# RK.net
KiCad netlist of a schematic drawn in EAGLE
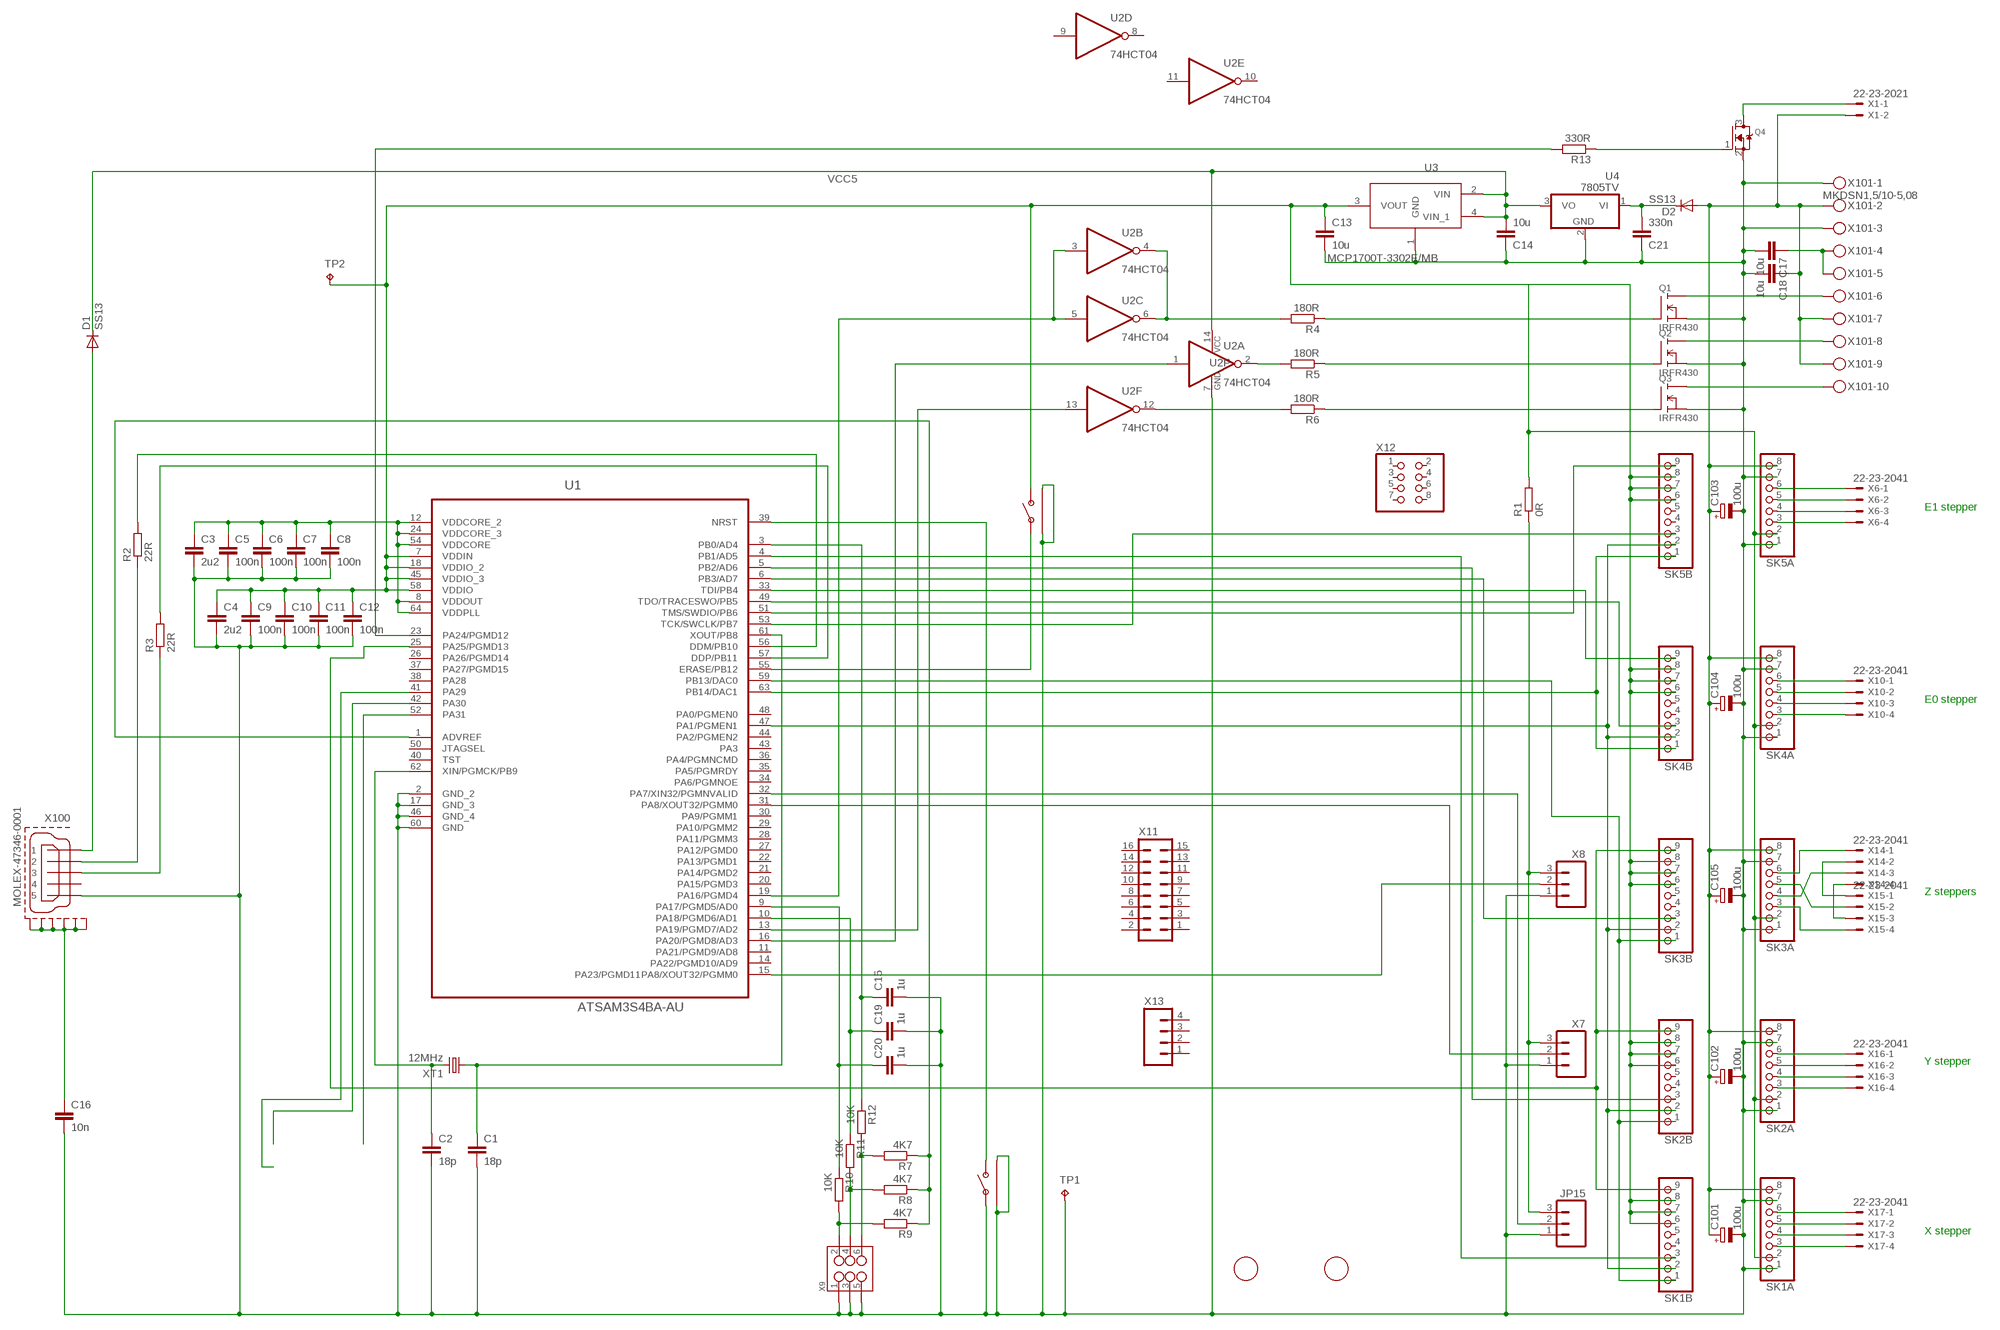
[diagram p0: schematic, sheet 1]

(export (version "E")
  (design (tool "Eeschema 10.0.6"))
  (components
    (comp (ref "C1")
      (value "18p")
      (footprint "eagle-import:C0603")
      (libsource (lib "eagle-import") (part "C-EUC0603"))
    )
    (comp (ref "C2")
      (value "18p")
      (footprint "eagle-import:C0603")
      (libsource (lib "eagle-import") (part "C-EUC0603"))
    )
    (comp (ref "C3")
      (value "2u2")
      (footprint "eagle-import:C0603")
      (libsource (lib "eagle-import") (part "C-EUC0603"))
    )
    (comp (ref "C4")
      (value "2u2")
      (footprint "eagle-import:C0603")
      (libsource (lib "eagle-import") (part "C-EUC0603"))
    )
    (comp (ref "C5")
      (value "100n")
      (footprint "eagle-import:C0603")
      (libsource (lib "eagle-import") (part "C-EUC0603"))
    )
    (comp (ref "C6")
      (value "100n")
      (footprint "eagle-import:C0603")
      (libsource (lib "eagle-import") (part "C-EUC0603"))
    )
    (comp (ref "C7")
      (value "100n")
      (footprint "eagle-import:C0603")
      (libsource (lib "eagle-import") (part "C-EUC0603"))
    )
    (comp (ref "C8")
      (value "100n")
      (footprint "eagle-import:C0603")
      (libsource (lib "eagle-import") (part "C-EUC0603"))
    )
    (comp (ref "C9")
      (value "100n")
      (footprint "eagle-import:C0603")
      (libsource (lib "eagle-import") (part "C-EUC0603"))
    )
    (comp (ref "C10")
      (value "100n")
      (footprint "eagle-import:C0603")
      (libsource (lib "eagle-import") (part "C-EUC0603"))
    )
    (comp (ref "C11")
      (value "100n")
      (footprint "eagle-import:C0603")
      (libsource (lib "eagle-import") (part "C-EUC0603"))
    )
    (comp (ref "C12")
      (value "100n")
      (footprint "eagle-import:C0603")
      (libsource (lib "eagle-import") (part "C-EUC0603"))
    )
    (comp (ref "C13")
      (value "10u")
      (footprint "eagle-import:C0805")
      (libsource (lib "eagle-import") (part "C-EUC0805"))
    )
    (comp (ref "C14")
      (value "10u")
      (footprint "eagle-import:C0805")
      (libsource (lib "eagle-import") (part "C-EUC0805"))
    )
    (comp (ref "C15")
      (value "1u")
      (footprint "eagle-import:C0603")
      (libsource (lib "eagle-import") (part "C-EUC0603"))
    )
    (comp (ref "C16")
      (value "10n")
      (footprint "eagle-import:C0603")
      (libsource (lib "eagle-import") (part "C-EUC0603"))
    )
    (comp (ref "C17")
      (value "10u")
      (footprint "eagle-import:C0805K")
      (libsource (lib "eagle-import") (part "C-EUC0805K"))
    )
    (comp (ref "C18")
      (value "10u")
      (footprint "eagle-import:C0805K")
      (libsource (lib "eagle-import") (part "C-EUC0805K"))
    )
    (comp (ref "C19")
      (value "1u")
      (footprint "eagle-import:C0603")
      (libsource (lib "eagle-import") (part "C-EUC0603"))
    )
    (comp (ref "C20")
      (value "1u")
      (footprint "eagle-import:C0603")
      (libsource (lib "eagle-import") (part "C-EUC0603"))
    )
    (comp (ref "C21")
      (value "330n")
      (footprint "eagle-import:C0805")
      (libsource (lib "eagle-import") (part "C-EUC0805"))
    )
    (comp (ref "C101")
      (value "100u")
      (footprint "eagle-import:PANASONIC_D")
      (libsource (lib "eagle-import") (part "CPOL-EUD"))
    )
    (comp (ref "C102")
      (value "100u")
      (footprint "eagle-import:PANASONIC_D")
      (libsource (lib "eagle-import") (part "CPOL-EUD"))
    )
    (comp (ref "C103")
      (value "100u")
      (footprint "eagle-import:PANASONIC_D")
      (libsource (lib "eagle-import") (part "CPOL-EUD"))
    )
    (comp (ref "C104")
      (value "100u")
      (footprint "eagle-import:PANASONIC_D")
      (libsource (lib "eagle-import") (part "CPOL-EUD"))
    )
    (comp (ref "C105")
      (value "100u")
      (footprint "eagle-import:PANASONIC_D")
      (libsource (lib "eagle-import") (part "CPOL-EUD"))
    )
    (comp (ref "D1")
      (value "SS13")
      (footprint "eagle-import:DO214AC")
      (libsource (lib "eagle-import") (part "DIODE-DO214AC"))
    )
    (comp (ref "D2")
      (value "SS13")
      (footprint "eagle-import:DO214AC")
      (libsource (lib "eagle-import") (part "DIODE-DO214AC"))
    )
    (comp (ref "JP15")
      (value "M03PTH")
      (footprint "eagle-import:1X03")
      (libsource (lib "eagle-import") (part "M03PTH"))
    )
    (comp (ref "Q1")
      (value "IRFR430")
      (footprint "eagle-import:DPAK")
      (libsource (lib "eagle-import") (part "IRFR430"))
    )
    (comp (ref "Q2")
      (value "IRFR430")
      (footprint "eagle-import:DPAK")
      (libsource (lib "eagle-import") (part "IRFR430"))
    )
    (comp (ref "Q3")
      (value "IRFR430")
      (footprint "eagle-import:DPAK")
      (libsource (lib "eagle-import") (part "IRFR430"))
    )
    (comp (ref "Q4")
      (value "MOSFET-NREFLOW")
      (footprint "eagle-import:SOT23")
      (libsource (lib "eagle-import") (part "MOSFET-NREFLOW"))
    )
    (comp (ref "R1")
      (value "0R")
      (footprint "eagle-import:R0603")
      (libsource (lib "eagle-import") (part "R-EU_R0603"))
    )
    (comp (ref "R2")
      (value "22R")
      (footprint "eagle-import:R0603")
      (libsource (lib "eagle-import") (part "R-EU_R0603"))
    )
    (comp (ref "R3")
      (value "22R")
      (footprint "eagle-import:R0603")
      (libsource (lib "eagle-import") (part "R-EU_R0603"))
    )
    (comp (ref "R4")
      (value "180R")
      (footprint "eagle-import:R0603")
      (libsource (lib "eagle-import") (part "R-EU_R0603"))
    )
    (comp (ref "R5")
      (value "180R")
      (footprint "eagle-import:R0603")
      (libsource (lib "eagle-import") (part "R-EU_R0603"))
    )
    (comp (ref "R6")
      (value "180R")
      (footprint "eagle-import:R0603")
      (libsource (lib "eagle-import") (part "R-EU_R0603"))
    )
    (comp (ref "R7")
      (value "4K7")
      (footprint "eagle-import:R0603")
      (libsource (lib "eagle-import") (part "R-EU_R0603"))
    )
    (comp (ref "R8")
      (value "4K7")
      (footprint "eagle-import:R0603")
      (libsource (lib "eagle-import") (part "R-EU_R0603"))
    )
    (comp (ref "R9")
      (value "4K7")
      (footprint "eagle-import:R0603")
      (libsource (lib "eagle-import") (part "R-EU_R0603"))
    )
    (comp (ref "R10")
      (value "10K")
      (footprint "eagle-import:R0603")
      (libsource (lib "eagle-import") (part "R-EU_R0603"))
    )
    (comp (ref "R11")
      (value "10K")
      (footprint "eagle-import:R0603")
      (libsource (lib "eagle-import") (part "R-EU_R0603"))
    )
    (comp (ref "R12")
      (value "10K")
      (footprint "eagle-import:R0603")
      (libsource (lib "eagle-import") (part "R-EU_R0603"))
    )
    (comp (ref "R13")
      (value "330R")
      (footprint "eagle-import:R0603")
      (libsource (lib "eagle-import") (part "R-EU_R0603"))
    )
    (comp (ref "SK1A")
      (value "PINHD-1X8BIG")
      (footprint "eagle-import:1X08-BIG")
      (libsource (lib "eagle-import") (part "PINHD-1X8BIG"))
    )
    (comp (ref "SK1B")
      (value "PINHD-1X9")
      (footprint "eagle-import:1X09-BIG")
      (libsource (lib "eagle-import") (part "PINHD-1X9"))
    )
    (comp (ref "SK2A")
      (value "PINHD-1X8BIG")
      (footprint "eagle-import:1X08-BIG")
      (libsource (lib "eagle-import") (part "PINHD-1X8BIG"))
    )
    (comp (ref "SK2B")
      (value "PINHD-1X9")
      (footprint "eagle-import:1X09-BIG")
      (libsource (lib "eagle-import") (part "PINHD-1X9"))
    )
    (comp (ref "SK3A")
      (value "PINHD-1X8BIG")
      (footprint "eagle-import:1X08-BIG")
      (libsource (lib "eagle-import") (part "PINHD-1X8BIG"))
    )
    (comp (ref "SK3B")
      (value "PINHD-1X9")
      (footprint "eagle-import:1X09-BIG")
      (libsource (lib "eagle-import") (part "PINHD-1X9"))
    )
    (comp (ref "SK4A")
      (value "PINHD-1X8BIG")
      (footprint "eagle-import:1X08-BIG")
      (libsource (lib "eagle-import") (part "PINHD-1X8BIG"))
    )
    (comp (ref "SK4B")
      (value "PINHD-1X9")
      (footprint "eagle-import:1X09-BIG")
      (libsource (lib "eagle-import") (part "PINHD-1X9"))
    )
    (comp (ref "SK5A")
      (value "PINHD-1X8BIG")
      (footprint "eagle-import:1X08-BIG")
      (libsource (lib "eagle-import") (part "PINHD-1X8BIG"))
    )
    (comp (ref "SK5B")
      (value "PINHD-1X9")
      (footprint "eagle-import:1X09-BIG")
      (libsource (lib "eagle-import") (part "PINHD-1X9"))
    )
    (comp (ref "TP1")
      (value "TPPAD1-10")
      (footprint "eagle-import:P1-10")
      (libsource (lib "eagle-import") (part "TPPAD1-10"))
    )
    (comp (ref "TP2")
      (value "TPPAD1-10")
      (footprint "eagle-import:P1-10")
      (libsource (lib "eagle-import") (part "TPPAD1-10"))
    )
    (comp (ref "U$1")
      (value "FIDUCIAL")
      (footprint "eagle-import:FIDUCIAL_1MM")
      (libsource (lib "eagle-import") (part "FIDUCIAL"))
    )
    (comp (ref "U$2")
      (value "FIDUCIAL")
      (footprint "eagle-import:FIDUCIAL_1MM")
      (libsource (lib "eagle-import") (part "FIDUCIAL"))
    )
    (comp (ref "U$3")
      (value "ALPS-SKHHLUA010")
      (footprint "eagle-import:SKHHLUA010")
      (libsource (lib "eagle-import") (part "ALPS-SKHHLUA010"))
    )
    (comp (ref "U$4")
      (value "ALPS-SKHHLUA010")
      (footprint "eagle-import:SKHHLUA010")
      (libsource (lib "eagle-import") (part "ALPS-SKHHLUA010"))
    )
    (comp (ref "U1")
      (value "ATSAM3S4BA-AU")
      (footprint "eagle-import:QFP50P1200X1200X160-64N")
      (libsource (lib "eagle-import") (part "ATSAM3S4BA-AU"))
    )
    (comp (ref "U2")
      (value "74HCT04")
      (footprint "eagle-import:TSSOP14")
      (libsource (lib "eagle-import") (part "7404"))
    )
    (comp (ref "U3")
      (value "MCP1700T-3302E/MB")
      (footprint "eagle-import:SOT150P400X160-4N")
      (fields (field (name "MPN") "MCP1702T-3302E/MB"))
      (libsource (lib "eagle-import") (part "MCP17-MCP1702T-3302E/MB"))
    )
    (comp (ref "U4")
      (value "7805TV")
      (footprint "eagle-import:TO220V")
      (libsource (lib "eagle-import") (part "78TV05"))
    )
    (comp (ref "X1")
      (value "22-23-2021")
      (footprint "eagle-import:22-23-2021")
      (fields (field (name "MF") "MOLEX"))
      (libsource (lib "eagle-import") (part "22-23-2021"))
    )
    (comp (ref "X6")
      (value "22-23-2041")
      (footprint "eagle-import:22-23-2041")
      (fields (field (name "MF") "MOLEX"))
      (libsource (lib "eagle-import") (part "22-23-2041"))
    )
    (comp (ref "X7")
      (value "M03PTH")
      (footprint "eagle-import:1X03")
      (libsource (lib "eagle-import") (part "M03PTH"))
    )
    (comp (ref "X8")
      (value "M03PTH")
      (footprint "eagle-import:1X03")
      (libsource (lib "eagle-import") (part "M03PTH"))
    )
    (comp (ref "X9")
      (value "M03X22X3_SILK_SM")
      (footprint "eagle-import:2X3")
      (libsource (lib "eagle-import") (part "M03X22X3_SILK_SM"))
    )
    (comp (ref "X10")
      (value "22-23-2041")
      (footprint "eagle-import:22-23-2041")
      (fields (field (name "MF") "MOLEX"))
      (libsource (lib "eagle-import") (part "22-23-2041"))
    )
    (comp (ref "X11")
      (value "MA08-2")
      (footprint "eagle-import:MA08-2")
      (libsource (lib "eagle-import") (part "MA08-2"))
    )
    (comp (ref "X12")
      (value "PINHD-2X4")
      (footprint "eagle-import:2X04")
      (libsource (lib "eagle-import") (part "PINHD-2X4"))
    )
    (comp (ref "X13")
      (value "M04PTH")
      (footprint "eagle-import:1X04")
      (libsource (lib "eagle-import") (part "M04PTH"))
    )
    (comp (ref "X14")
      (value "22-23-2041")
      (footprint "eagle-import:22-23-2041")
      (fields (field (name "MF") "MOLEX"))
      (libsource (lib "eagle-import") (part "22-23-2041"))
    )
    (comp (ref "X15")
      (value "22-23-2041")
      (footprint "eagle-import:22-23-2041")
      (fields (field (name "MF") "MOLEX"))
      (libsource (lib "eagle-import") (part "22-23-2041"))
    )
    (comp (ref "X16")
      (value "22-23-2041")
      (footprint "eagle-import:22-23-2041")
      (fields (field (name "MF") "MOLEX"))
      (libsource (lib "eagle-import") (part "22-23-2041"))
    )
    (comp (ref "X17")
      (value "22-23-2041")
      (footprint "eagle-import:22-23-2041")
      (fields (field (name "MF") "MOLEX"))
      (libsource (lib "eagle-import") (part "22-23-2041"))
    )
    (comp (ref "X100")
      (value "MOLEX-47346-0001")
      (footprint "eagle-import:MOLEX-47364-0001")
      (libsource (lib "eagle-import") (part "MOLEX-47346-0001"))
    )
    (comp (ref "X101")
      (value "MKDSN1,5/10-5,08")
      (footprint "eagle-import:MKDSN1,5_10-5,08")
      (fields (field (name "MPN") "SMKDSN1,5/10-5,08"))
      (libsource (lib "eagle-import") (part "MKDSN1,5/10-5,08"))
    )
    (comp (ref "XT1")
      (value "12MHz")
      (footprint "eagle-import:HC49U-V")
      (libsource (lib "eagle-import") (part "CRYSTALHC49U-V"))
    )
  )
  (nets
    (net (code "1") (name "/VCC5") (class "Default")
      (node (ref "C14") (pin "2") (pinfunction "2_2") (pintype "passive"))
      (node (ref "D1") (pin "C") (pinfunction "C_C") (pintype "passive"))
      (node (ref "U2") (pin "14") (pinfunction "VCC_14") (pintype "power_in"))
      (node (ref "U3") (pin "2") (pinfunction "VIN_2") (pintype "input"))
      (node (ref "U3") (pin "4") (pinfunction "VIN_1_4") (pintype "input"))
      (node (ref "U4") (pin "3") (pinfunction "VO_3") (pintype "passive"))
    )
    (net (code "2") (name "Net-(C16-Pad1)") (class "Default")
      (node (ref "C16") (pin "1") (pinfunction "1_1") (pintype "passive"))
      (node (ref "X100") (pin "GND1") (pinfunction "GND1_GND1") (pintype "bidirectional"))
      (node (ref "X100") (pin "GND2") (pinfunction "GND2_GND2") (pintype "bidirectional"))
      (node (ref "X100") (pin "GND3") (pinfunction "GND3_GND3") (pintype "bidirectional"))
      (node (ref "X100") (pin "GND4") (pinfunction "GND4_GND4") (pintype "bidirectional"))
      (node (ref "X100") (pin "GND5") (pinfunction "GND5_GND5") (pintype "bidirectional"))
      (node (ref "X100") (pin "GND6") (pinfunction "GND6_GND6") (pintype "bidirectional"))
    )
    (net (code "3") (name "Net-(D1-PadA)") (class "Default")
      (node (ref "D1") (pin "A") (pinfunction "A_A") (pintype "passive"))
      (node (ref "X100") (pin "1") (pinfunction "1_1") (pintype "input"))
    )
    (net (code "4") (name "Net-(JP15-Pad3)") (class "Default")
      (node (ref "JP15") (pin "3") (pinfunction "3_3") (pintype "passive"))
      (node (ref "R1") (pin "1") (pinfunction "1_1") (pintype "passive"))
      (node (ref "X7") (pin "3") (pinfunction "3_3") (pintype "passive"))
      (node (ref "X8") (pin "3") (pinfunction "3_3") (pintype "passive"))
    )
    (net (code "5") (name "Net-(Q1-D)") (class "Default")
      (node (ref "Q1") (pin "2") (pinfunction "D_2") (pintype "passive"))
      (node (ref "X101") (pin "6") (pinfunction "KL_6") (pintype "passive"))
    )
    (net (code "6") (name "Net-(Q1-G)") (class "Default")
      (node (ref "Q1") (pin "1") (pinfunction "G_1") (pintype "passive"))
      (node (ref "R4") (pin "1") (pinfunction "1_1") (pintype "passive"))
    )
    (net (code "7") (name "Net-(Q1-S)") (class "Default")
      (node (ref "C1") (pin "2") (pinfunction "2_2") (pintype "passive"))
      (node (ref "C10") (pin "2") (pinfunction "2_2") (pintype "passive"))
      (node (ref "C101") (pin "-") (pinfunction "-_-") (pintype "passive"))
      (node (ref "C102") (pin "-") (pinfunction "-_-") (pintype "passive"))
      (node (ref "C103") (pin "-") (pinfunction "-_-") (pintype "passive"))
      (node (ref "C104") (pin "-") (pinfunction "-_-") (pintype "passive"))
      (node (ref "C105") (pin "-") (pinfunction "-_-") (pintype "passive"))
      (node (ref "C11") (pin "2") (pinfunction "2_2") (pintype "passive"))
      (node (ref "C12") (pin "2") (pinfunction "2_2") (pintype "passive"))
      (node (ref "C13") (pin "2") (pinfunction "2_2") (pintype "passive"))
      (node (ref "C14") (pin "1") (pinfunction "1_1") (pintype "passive"))
      (node (ref "C15") (pin "2") (pinfunction "2_2") (pintype "passive"))
      (node (ref "C16") (pin "2") (pinfunction "2_2") (pintype "passive"))
      (node (ref "C17") (pin "2") (pinfunction "2_2") (pintype "passive"))
      (node (ref "C18") (pin "2") (pinfunction "2_2") (pintype "passive"))
      (node (ref "C19") (pin "2") (pinfunction "2_2") (pintype "passive"))
      (node (ref "C2") (pin "2") (pinfunction "2_2") (pintype "passive"))
      (node (ref "C20") (pin "2") (pinfunction "2_2") (pintype "passive"))
      (node (ref "C21") (pin "1") (pinfunction "1_1") (pintype "passive"))
      (node (ref "C3") (pin "2") (pinfunction "2_2") (pintype "passive"))
      (node (ref "C4") (pin "2") (pinfunction "2_2") (pintype "passive"))
      (node (ref "C5") (pin "2") (pinfunction "2_2") (pintype "passive"))
      (node (ref "C6") (pin "2") (pinfunction "2_2") (pintype "passive"))
      (node (ref "C7") (pin "2") (pinfunction "2_2") (pintype "passive"))
      (node (ref "C8") (pin "2") (pinfunction "2_2") (pintype "passive"))
      (node (ref "C9") (pin "2") (pinfunction "2_2") (pintype "passive"))
      (node (ref "JP15") (pin "1") (pinfunction "1_1") (pintype "passive"))
      (node (ref "Q1") (pin "3") (pinfunction "S_3") (pintype "passive"))
      (node (ref "Q2") (pin "3") (pinfunction "S_3") (pintype "passive"))
      (node (ref "Q3") (pin "3") (pinfunction "S_3") (pintype "passive"))
      (node (ref "Q4") (pin "2") (pinfunction "S_2") (pintype "bidirectional"))
      (node (ref "SK1A") (pin "1") (pinfunction "1_1") (pintype "passive"))
      (node (ref "SK1A") (pin "7") (pinfunction "7_7") (pintype "passive"))
      (node (ref "SK2A") (pin "1") (pinfunction "1_1") (pintype "passive"))
      (node (ref "SK2A") (pin "7") (pinfunction "7_7") (pintype "passive"))
      (node (ref "SK3A") (pin "1") (pinfunction "1_1") (pintype "passive"))
      (node (ref "SK3A") (pin "7") (pinfunction "7_7") (pintype "passive"))
      (node (ref "SK4A") (pin "1") (pinfunction "1_1") (pintype "passive"))
      (node (ref "SK4A") (pin "7") (pinfunction "7_7") (pintype "passive"))
      (node (ref "SK5A") (pin "1") (pinfunction "1_1") (pintype "passive"))
      (node (ref "SK5A") (pin "7") (pinfunction "7_7") (pintype "passive"))
      (node (ref "TP1") (pin "TP") (pinfunction "TP_TP") (pintype "input"))
      (node (ref "U$3") (pin "P$1") (pinfunction "P$1_P$1") (pintype "bidirectional"))
      (node (ref "U$3") (pin "P$3") (pinfunction "P$3_P$3") (pintype "bidirectional"))
      (node (ref "U$3") (pin "P$4") (pinfunction "P$4_P$4") (pintype "bidirectional"))
      (node (ref "U$4") (pin "P$3") (pinfunction "P$3_P$3") (pintype "bidirectional"))
      (node (ref "U$4") (pin "P$4") (pinfunction "P$4_P$4") (pintype "bidirectional"))
      (node (ref "U1") (pin "17") (pinfunction "GND_3_17") (pintype "passive"))
      (node (ref "U1") (pin "2") (pinfunction "GND_2_2") (pintype "passive"))
      (node (ref "U1") (pin "46") (pinfunction "GND_4_46") (pintype "passive"))
      (node (ref "U1") (pin "60") (pinfunction "GND_60") (pintype "passive"))
      (node (ref "U2") (pin "7") (pinfunction "GND_7") (pintype "power_in"))
      (node (ref "U3") (pin "1") (pinfunction "GND_1") (pintype "power_in"))
      (node (ref "U4") (pin "2") (pinfunction "GND_2") (pintype "passive"))
      (node (ref "X100") (pin "5") (pinfunction "5_5") (pintype "input"))
      (node (ref "X101") (pin "1") (pinfunction "KL_1") (pintype "passive"))
      (node (ref "X101") (pin "3") (pinfunction "KL_3") (pintype "passive"))
      (node (ref "X7") (pin "1") (pinfunction "1_1") (pintype "passive"))
      (node (ref "X8") (pin "1") (pinfunction "1_1") (pintype "passive"))
      (node (ref "X9") (pin "1") (pinfunction "1_1") (pintype "bidirectional"))
      (node (ref "X9") (pin "3") (pinfunction "3_3") (pintype "bidirectional"))
      (node (ref "X9") (pin "5") (pinfunction "5_5") (pintype "bidirectional"))
    )
    (net (code "8") (name "Net-(Q2-D)") (class "Default")
      (node (ref "Q2") (pin "2") (pinfunction "D_2") (pintype "passive"))
      (node (ref "X101") (pin "8") (pinfunction "KL_8") (pintype "passive"))
    )
    (net (code "9") (name "Net-(Q2-G)") (class "Default")
      (node (ref "Q2") (pin "1") (pinfunction "G_1") (pintype "passive"))
      (node (ref "R5") (pin "1") (pinfunction "1_1") (pintype "passive"))
    )
    (net (code "10") (name "Net-(Q3-D)") (class "Default")
      (node (ref "Q3") (pin "2") (pinfunction "D_2") (pintype "passive"))
      (node (ref "X101") (pin "10") (pinfunction "KL_10") (pintype "passive"))
    )
    (net (code "11") (name "Net-(Q3-G)") (class "Default")
      (node (ref "Q3") (pin "1") (pinfunction "G_1") (pintype "passive"))
      (node (ref "R6") (pin "1") (pinfunction "1_1") (pintype "passive"))
    )
    (net (code "12") (name "Net-(Q4-D)") (class "Default")
      (node (ref "Q4") (pin "3") (pinfunction "D_3") (pintype "bidirectional"))
      (node (ref "X1") (pin "1") (pinfunction "S_1") (pintype "passive"))
    )
    (net (code "13") (name "Net-(Q4-G)") (class "Default")
      (node (ref "Q4") (pin "1") (pinfunction "G_1") (pintype "bidirectional"))
      (node (ref "R13") (pin "1") (pinfunction "1_1") (pintype "passive"))
    )
    (net (code "14") (name "Net-(R2-Pad1)") (class "Default")
      (node (ref "R2") (pin "1") (pinfunction "1_1") (pintype "passive"))
      (node (ref "X100") (pin "2") (pinfunction "2_2") (pintype "input"))
    )
    (net (code "15") (name "Net-(R3-Pad1)") (class "Default")
      (node (ref "R3") (pin "1") (pinfunction "1_1") (pintype "passive"))
      (node (ref "X100") (pin "3") (pinfunction "3_3") (pintype "input"))
    )
    (net (code "16") (name "Net-(R10-Pad2)") (class "Default")
      (node (ref "R10") (pin "2") (pinfunction "2_2") (pintype "passive"))
      (node (ref "R9") (pin "2") (pinfunction "2_2") (pintype "passive"))
      (node (ref "X9") (pin "2") (pinfunction "2_2") (pintype "bidirectional"))
    )
    (net (code "17") (name "Net-(R11-Pad2)") (class "Default")
      (node (ref "R11") (pin "2") (pinfunction "2_2") (pintype "passive"))
      (node (ref "R8") (pin "2") (pinfunction "2_2") (pintype "passive"))
      (node (ref "X9") (pin "4") (pinfunction "4_4") (pintype "bidirectional"))
    )
    (net (code "18") (name "Net-(R12-Pad2)") (class "Default")
      (node (ref "R12") (pin "2") (pinfunction "2_2") (pintype "passive"))
      (node (ref "R7") (pin "2") (pinfunction "2_2") (pintype "passive"))
      (node (ref "X9") (pin "6") (pinfunction "6_6") (pintype "bidirectional"))
    )
    (net (code "19") (name "Net-(U1-ADVREF)") (class "Default")
      (node (ref "R7") (pin "1") (pinfunction "1_1") (pintype "passive"))
      (node (ref "R8") (pin "1") (pinfunction "1_1") (pintype "passive"))
      (node (ref "R9") (pin "1") (pinfunction "1_1") (pintype "passive"))
      (node (ref "U1") (pin "1") (pinfunction "ADVREF_1") (pintype "input"))
    )
    (net (code "20") (name "Net-(U1-DDM{slash}PB10)") (class "Default")
      (node (ref "R2") (pin "2") (pinfunction "2_2") (pintype "passive"))
      (node (ref "U1") (pin "56") (pinfunction "DDM/PB10_56") (pintype "bidirectional"))
    )
    (net (code "21") (name "Net-(U1-DDP{slash}PB11)") (class "Default")
      (node (ref "R3") (pin "2") (pinfunction "2_2") (pintype "passive"))
      (node (ref "U1") (pin "57") (pinfunction "DDP/PB11_57") (pintype "bidirectional"))
    )
    (net (code "22") (name "Net-(U1-ERASE{slash}PB12)") (class "Default")
      (node (ref "U$4") (pin "P$1") (pinfunction "P$1_P$1") (pintype "bidirectional"))
      (node (ref "U1") (pin "55") (pinfunction "ERASE/PB12_55") (pintype "bidirectional"))
    )
    (net (code "23") (name "Net-(U1-NRST)") (class "Default")
      (node (ref "U$3") (pin "P$2") (pinfunction "P$2_P$2") (pintype "bidirectional"))
      (node (ref "U1") (pin "39") (pinfunction "NRST_39") (pintype "bidirectional"))
    )
    (net (code "24") (name "Net-(U1-PA1{slash}PGMEN1)") (class "Default")
      (node (ref "SK1B") (pin "2") (pinfunction "2_2") (pintype "passive"))
      (node (ref "SK2B") (pin "2") (pinfunction "2_2") (pintype "passive"))
      (node (ref "SK3B") (pin "2") (pinfunction "2_2") (pintype "passive"))
      (node (ref "SK4B") (pin "2") (pinfunction "2_2") (pintype "passive"))
      (node (ref "SK5B") (pin "2") (pinfunction "2_2") (pintype "passive"))
      (node (ref "U1") (pin "47") (pinfunction "PA1/PGMEN1_47") (pintype "bidirectional"))
    )
    (net (code "25") (name "Net-(U1-PA7{slash}XIN32{slash}PGMNVALID)") (class "Default")
      (node (ref "JP15") (pin "2") (pinfunction "2_2") (pintype "passive"))
      (node (ref "U1") (pin "32") (pinfunction "PA7/XIN32/PGMNVALID_32") (pintype "bidirectional"))
    )
    (net (code "26") (name "Net-(U1-PA8{slash}XOUT32{slash}PGMM0)") (class "Default")
      (node (ref "U1") (pin "31") (pinfunction "PA8/XOUT32/PGMM0_31") (pintype "bidirectional"))
      (node (ref "X7") (pin "2") (pinfunction "2_2") (pintype "passive"))
    )
    (net (code "27") (name "Net-(U1-PA16{slash}PGMD4)") (class "Default")
      (node (ref "U1") (pin "19") (pinfunction "PA16/PGMD4_19") (pintype "bidirectional"))
      (node (ref "U2") (pin "3") (pinfunction "I_3") (pintype "input"))
      (node (ref "U2") (pin "5") (pinfunction "I_5") (pintype "input"))
    )
    (net (code "28") (name "Net-(U1-PA17{slash}PGMD5{slash}AD0)") (class "Default")
      (node (ref "C20") (pin "1") (pinfunction "1_1") (pintype "passive"))
      (node (ref "R10") (pin "1") (pinfunction "1_1") (pintype "passive"))
      (node (ref "U1") (pin "9") (pinfunction "PA17/PGMD5/AD0_9") (pintype "bidirectional"))
    )
    (net (code "29") (name "Net-(U1-PA18{slash}PGMD6{slash}AD1)") (class "Default")
      (node (ref "C19") (pin "1") (pinfunction "1_1") (pintype "passive"))
      (node (ref "R11") (pin "1") (pinfunction "1_1") (pintype "passive"))
      (node (ref "U1") (pin "10") (pinfunction "PA18/PGMD6/AD1_10") (pintype "bidirectional"))
    )
    (net (code "30") (name "Net-(U1-PA19{slash}PGMD7{slash}AD2)") (class "Default")
      (node (ref "U1") (pin "13") (pinfunction "PA19/PGMD7/AD2_13") (pintype "bidirectional"))
      (node (ref "U2") (pin "13") (pinfunction "I_13") (pintype "input"))
    )
    (net (code "31") (name "Net-(U1-PA20{slash}PGMD8{slash}AD3)") (class "Default")
      (node (ref "U1") (pin "16") (pinfunction "PA20/PGMD8/AD3_16") (pintype "bidirectional"))
      (node (ref "U2") (pin "1") (pinfunction "I_1") (pintype "input"))
    )
    (net (code "32") (name "Net-(U1-PA23{slash}PGMD11PA8{slash}XOUT32{slash}PGMM0)") (class "Default")
      (node (ref "U1") (pin "15") (pinfunction "PA23/PGMD11PA8/XOUT32/PGMM0_15") (pintype "bidirectional"))
      (node (ref "X8") (pin "2") (pinfunction "2_2") (pintype "passive"))
    )
    (net (code "33") (name "Net-(U1-PA24{slash}PGMD12)") (class "Default")
      (node (ref "R13") (pin "2") (pinfunction "2_2") (pintype "passive"))
      (node (ref "U1") (pin "23") (pinfunction "PA24/PGMD12_23") (pintype "bidirectional"))
    )
    (net (code "34") (name "Net-(U1-PA25{slash}PGMD13)") (class "Default")
      (node (ref "SK1B") (pin "9") (pinfunction "9_9") (pintype "passive"))
      (node (ref "SK2B") (pin "9") (pinfunction "9_9") (pintype "passive"))
      (node (ref "SK3B") (pin "9") (pinfunction "9_9") (pintype "passive"))
      (node (ref "U1") (pin "25") (pinfunction "PA25/PGMD13_25") (pintype "bidirectional"))
    )
    (net (code "35") (name "Net-(U1-PB0{slash}AD4)") (class "Default")
      (node (ref "C15") (pin "1") (pinfunction "1_1") (pintype "passive"))
      (node (ref "R12") (pin "1") (pinfunction "1_1") (pintype "passive"))
      (node (ref "U1") (pin "3") (pinfunction "PB0/AD4_3") (pintype "bidirectional"))
    )
    (net (code "36") (name "Net-(U1-PB1{slash}AD5)") (class "Default")
      (node (ref "SK1B") (pin "3") (pinfunction "3_3") (pintype "passive"))
      (node (ref "U1") (pin "4") (pinfunction "PB1/AD5_4") (pintype "bidirectional"))
    )
    (net (code "37") (name "Net-(U1-PB2{slash}AD6)") (class "Default")
      (node (ref "SK2B") (pin "3") (pinfunction "3_3") (pintype "passive"))
      (node (ref "U1") (pin "5") (pinfunction "PB2/AD6_5") (pintype "bidirectional"))
    )
    (net (code "38") (name "Net-(U1-PB3{slash}AD7)") (class "Default")
      (node (ref "SK3B") (pin "3") (pinfunction "3_3") (pintype "passive"))
      (node (ref "U1") (pin "6") (pinfunction "PB3/AD7_6") (pintype "bidirectional"))
    )
    (net (code "39") (name "Net-(U1-PB13{slash}DAC0)") (class "Default")
      (node (ref "SK1B") (pin "1") (pinfunction "1_1") (pintype "passive"))
      (node (ref "SK2B") (pin "1") (pinfunction "1_1") (pintype "passive"))
      (node (ref "SK3B") (pin "1") (pinfunction "1_1") (pintype "passive"))
      (node (ref "U1") (pin "59") (pinfunction "PB13/DAC0_59") (pintype "bidirectional"))
    )
    (net (code "40") (name "Net-(U1-PB14{slash}DAC1)") (class "Default")
      (node (ref "SK4B") (pin "1") (pinfunction "1_1") (pintype "passive"))
      (node (ref "SK5B") (pin "1") (pinfunction "1_1") (pintype "passive"))
      (node (ref "U1") (pin "63") (pinfunction "PB14/DAC1_63") (pintype "bidirectional"))
    )
    (net (code "41") (name "Net-(U1-TCK{slash}SWCLK{slash}PB7)") (class "Default")
      (node (ref "SK5B") (pin "3") (pinfunction "3_3") (pintype "passive"))
      (node (ref "U1") (pin "53") (pinfunction "TCK/SWCLK/PB7_53") (pintype "bidirectional"))
    )
    (net (code "42") (name "Net-(U1-TDI{slash}PB4)") (class "Default")
      (node (ref "SK4B") (pin "9") (pinfunction "9_9") (pintype "passive"))
      (node (ref "U1") (pin "33") (pinfunction "TDI/PB4_33") (pintype "bidirectional"))
    )
    (net (code "43") (name "Net-(U1-TDO{slash}TRACESWO{slash}PB5)") (class "Default")
      (node (ref "SK4B") (pin "3") (pinfunction "3_3") (pintype "passive"))
      (node (ref "U1") (pin "49") (pinfunction "TDO/TRACESWO/PB5_49") (pintype "bidirectional"))
    )
    (net (code "44") (name "Net-(U1-TMS{slash}SWDIO{slash}PB6)") (class "Default")
      (node (ref "SK5B") (pin "9") (pinfunction "9_9") (pintype "passive"))
      (node (ref "U1") (pin "51") (pinfunction "TMS/SWDIO/PB6_51") (pintype "bidirectional"))
    )
    (net (code "45") (name "Net-(U1-VDDCORE)") (class "Default")
      (node (ref "C3") (pin "1") (pinfunction "1_1") (pintype "passive"))
      (node (ref "C5") (pin "1") (pinfunction "1_1") (pintype "passive"))
      (node (ref "C6") (pin "1") (pinfunction "1_1") (pintype "passive"))
      (node (ref "C7") (pin "1") (pinfunction "1_1") (pintype "passive"))
      (node (ref "C8") (pin "1") (pinfunction "1_1") (pintype "passive"))
      (node (ref "U1") (pin "12") (pinfunction "VDDCORE_2_12") (pintype "power_in"))
      (node (ref "U1") (pin "24") (pinfunction "VDDCORE_3_24") (pintype "power_in"))
      (node (ref "U1") (pin "54") (pinfunction "VDDCORE_54") (pintype "power_in"))
      (node (ref "U1") (pin "64") (pinfunction "VDDPLL_64") (pintype "power_in"))
      (node (ref "U1") (pin "8") (pinfunction "VDDOUT_8") (pintype "power_in"))
    )
    (net (code "46") (name "Net-(U1-VDDIN)") (class "Default")
      (node (ref "C10") (pin "1") (pinfunction "1_1") (pintype "passive"))
      (node (ref "C11") (pin "1") (pinfunction "1_1") (pintype "passive"))
      (node (ref "C12") (pin "1") (pinfunction "1_1") (pintype "passive"))
      (node (ref "C13") (pin "1") (pinfunction "1_1") (pintype "passive"))
      (node (ref "C4") (pin "1") (pinfunction "1_1") (pintype "passive"))
      (node (ref "C9") (pin "1") (pinfunction "1_1") (pintype "passive"))
      (node (ref "R1") (pin "2") (pinfunction "2_2") (pintype "passive"))
      (node (ref "SK1A") (pin "2") (pinfunction "2_2") (pintype "passive"))
      (node (ref "SK1B") (pin "6") (pinfunction "6_6") (pintype "passive"))
      (node (ref "SK1B") (pin "7") (pinfunction "7_7") (pintype "passive"))
      (node (ref "SK1B") (pin "8") (pinfunction "8_8") (pintype "passive"))
      (node (ref "SK2A") (pin "2") (pinfunction "2_2") (pintype "passive"))
      (node (ref "SK2B") (pin "6") (pinfunction "6_6") (pintype "passive"))
      (node (ref "SK2B") (pin "7") (pinfunction "7_7") (pintype "passive"))
      (node (ref "SK2B") (pin "8") (pinfunction "8_8") (pintype "passive"))
      (node (ref "SK3A") (pin "2") (pinfunction "2_2") (pintype "passive"))
      (node (ref "SK3B") (pin "6") (pinfunction "6_6") (pintype "passive"))
      (node (ref "SK3B") (pin "7") (pinfunction "7_7") (pintype "passive"))
      (node (ref "SK3B") (pin "8") (pinfunction "8_8") (pintype "passive"))
      (node (ref "SK4A") (pin "2") (pinfunction "2_2") (pintype "passive"))
      (node (ref "SK4B") (pin "6") (pinfunction "6_6") (pintype "passive"))
      (node (ref "SK4B") (pin "7") (pinfunction "7_7") (pintype "passive"))
      (node (ref "SK4B") (pin "8") (pinfunction "8_8") (pintype "passive"))
      (node (ref "SK5A") (pin "2") (pinfunction "2_2") (pintype "passive"))
      (node (ref "SK5B") (pin "6") (pinfunction "6_6") (pintype "passive"))
      (node (ref "SK5B") (pin "7") (pinfunction "7_7") (pintype "passive"))
      (node (ref "SK5B") (pin "8") (pinfunction "8_8") (pintype "passive"))
      (node (ref "TP2") (pin "TP") (pinfunction "TP_TP") (pintype "input"))
      (node (ref "U$4") (pin "P$2") (pinfunction "P$2_P$2") (pintype "bidirectional"))
      (node (ref "U1") (pin "18") (pinfunction "VDDIO_2_18") (pintype "power_in"))
      (node (ref "U1") (pin "45") (pinfunction "VDDIO_3_45") (pintype "power_in"))
      (node (ref "U1") (pin "58") (pinfunction "VDDIO_58") (pintype "power_in"))
      (node (ref "U1") (pin "7") (pinfunction "VDDIN_7") (pintype "power_in"))
      (node (ref "U3") (pin "3") (pinfunction "VOUT_3") (pintype "output"))
    )
    (net (code "47") (name "Net-(U1-XIN{slash}PGMCK{slash}PB9)") (class "Default")
      (node (ref "C2") (pin "1") (pinfunction "1_1") (pintype "passive"))
      (node (ref "U1") (pin "62") (pinfunction "XIN/PGMCK/PB9_62") (pintype "input"))
      (node (ref "XT1") (pin "2") (pinfunction "2_2") (pintype "passive"))
    )
    (net (code "48") (name "Net-(U1-XOUT{slash}PB8)") (class "Default")
      (node (ref "C1") (pin "1") (pinfunction "1_1") (pintype "passive"))
      (node (ref "U1") (pin "61") (pinfunction "XOUT/PB8_61") (pintype "output"))
      (node (ref "XT1") (pin "1") (pinfunction "1_1") (pintype "passive"))
    )
    (net (code "49") (name "Net-(U2A-O)") (class "Default")
      (node (ref "R5") (pin "2") (pinfunction "2_2") (pintype "passive"))
      (node (ref "U2") (pin "2") (pinfunction "O_2") (pintype "output"))
    )
    (net (code "50") (name "Net-(U2B-O)") (class "Default")
      (node (ref "R4") (pin "2") (pinfunction "2_2") (pintype "passive"))
      (node (ref "U2") (pin "4") (pinfunction "O_4") (pintype "output"))
      (node (ref "U2") (pin "6") (pinfunction "O_6") (pintype "output"))
    )
    (net (code "51") (name "Net-(U2F-O)") (class "Default")
      (node (ref "R6") (pin "2") (pinfunction "2_2") (pintype "passive"))
      (node (ref "U2") (pin "12") (pinfunction "O_12") (pintype "output"))
    )
    (net (code "52") (name "Net-(U4-VI)") (class "Default")
      (node (ref "C21") (pin "2") (pinfunction "2_2") (pintype "passive"))
      (node (ref "D2") (pin "C") (pinfunction "C_C") (pintype "passive"))
      (node (ref "U4") (pin "1") (pinfunction "VI_1") (pintype "input"))
    )
    (net (code "53") (name "Net-(X6A-S)") (class "Default")
      (node (ref "SK5A") (pin "6") (pinfunction "6_6") (pintype "passive"))
      (node (ref "X6") (pin "1") (pinfunction "S_1") (pintype "passive"))
    )
    (net (code "54") (name "Net-(X6B-S)") (class "Default")
      (node (ref "SK5A") (pin "5") (pinfunction "5_5") (pintype "passive"))
      (node (ref "X6") (pin "2") (pinfunction "S_2") (pintype "passive"))
    )
    (net (code "55") (name "Net-(X6C-S)") (class "Default")
      (node (ref "SK5A") (pin "4") (pinfunction "4_4") (pintype "passive"))
      (node (ref "X6") (pin "3") (pinfunction "S_3") (pintype "passive"))
    )
    (net (code "56") (name "Net-(X6D-S)") (class "Default")
      (node (ref "SK5A") (pin "3") (pinfunction "3_3") (pintype "passive"))
      (node (ref "X6") (pin "4") (pinfunction "S_4") (pintype "passive"))
    )
    (net (code "57") (name "Net-(X10A-S)") (class "Default")
      (node (ref "SK4A") (pin "6") (pinfunction "6_6") (pintype "passive"))
      (node (ref "X10") (pin "1") (pinfunction "S_1") (pintype "passive"))
    )
    (net (code "58") (name "Net-(X10B-S)") (class "Default")
      (node (ref "SK4A") (pin "5") (pinfunction "5_5") (pintype "passive"))
      (node (ref "X10") (pin "2") (pinfunction "S_2") (pintype "passive"))
    )
    (net (code "59") (name "Net-(X10C-S)") (class "Default")
      (node (ref "SK4A") (pin "4") (pinfunction "4_4") (pintype "passive"))
      (node (ref "X10") (pin "3") (pinfunction "S_3") (pintype "passive"))
    )
    (net (code "60") (name "Net-(X10D-S)") (class "Default")
      (node (ref "SK4A") (pin "3") (pinfunction "3_3") (pintype "passive"))
      (node (ref "X10") (pin "4") (pinfunction "S_4") (pintype "passive"))
    )
    (net (code "61") (name "Net-(X14A-S)") (class "Default")
      (node (ref "SK3A") (pin "6") (pinfunction "6_6") (pintype "passive"))
      (node (ref "X14") (pin "1") (pinfunction "S_1") (pintype "passive"))
    )
    (net (code "62") (name "Net-(X14B-S)") (class "Default")
      (node (ref "X14") (pin "2") (pinfunction "S_2") (pintype "passive"))
      (node (ref "X15") (pin "1") (pinfunction "S_1") (pintype "passive"))
    )
    (net (code "63") (name "Net-(X14C-S)") (class "Default")
      (node (ref "SK3A") (pin "4") (pinfunction "4_4") (pintype "passive"))
      (node (ref "X14") (pin "3") (pinfunction "S_3") (pintype "passive"))
    )
    (net (code "64") (name "Net-(X14D-S)") (class "Default")
      (node (ref "X14") (pin "4") (pinfunction "S_4") (pintype "passive"))
      (node (ref "X15") (pin "3") (pinfunction "S_3") (pintype "passive"))
    )
    (net (code "65") (name "Net-(X15B-S)") (class "Default")
      (node (ref "SK3A") (pin "5") (pinfunction "5_5") (pintype "passive"))
      (node (ref "X15") (pin "2") (pinfunction "S_2") (pintype "passive"))
    )
    (net (code "66") (name "Net-(X15D-S)") (class "Default")
      (node (ref "SK3A") (pin "3") (pinfunction "3_3") (pintype "passive"))
      (node (ref "X15") (pin "4") (pinfunction "S_4") (pintype "passive"))
    )
    (net (code "67") (name "Net-(X16A-S)") (class "Default")
      (node (ref "SK2A") (pin "6") (pinfunction "6_6") (pintype "passive"))
      (node (ref "X16") (pin "1") (pinfunction "S_1") (pintype "passive"))
    )
    (net (code "68") (name "Net-(X16B-S)") (class "Default")
      (node (ref "SK2A") (pin "5") (pinfunction "5_5") (pintype "passive"))
      (node (ref "X16") (pin "2") (pinfunction "S_2") (pintype "passive"))
    )
    (net (code "69") (name "Net-(X16C-S)") (class "Default")
      (node (ref "SK2A") (pin "4") (pinfunction "4_4") (pintype "passive"))
      (node (ref "X16") (pin "3") (pinfunction "S_3") (pintype "passive"))
    )
    (net (code "70") (name "Net-(X16D-S)") (class "Default")
      (node (ref "SK2A") (pin "3") (pinfunction "3_3") (pintype "passive"))
      (node (ref "X16") (pin "4") (pinfunction "S_4") (pintype "passive"))
    )
    (net (code "71") (name "Net-(X17A-S)") (class "Default")
      (node (ref "SK1A") (pin "6") (pinfunction "6_6") (pintype "passive"))
      (node (ref "X17") (pin "1") (pinfunction "S_1") (pintype "passive"))
    )
    (net (code "72") (name "Net-(X17B-S)") (class "Default")
      (node (ref "SK1A") (pin "5") (pinfunction "5_5") (pintype "passive"))
      (node (ref "X17") (pin "2") (pinfunction "S_2") (pintype "passive"))
    )
    (net (code "73") (name "Net-(X17C-S)") (class "Default")
      (node (ref "SK1A") (pin "4") (pinfunction "4_4") (pintype "passive"))
      (node (ref "X17") (pin "3") (pinfunction "S_3") (pintype "passive"))
    )
    (net (code "74") (name "Net-(X17D-S)") (class "Default")
      (node (ref "SK1A") (pin "3") (pinfunction "3_3") (pintype "passive"))
      (node (ref "X17") (pin "4") (pinfunction "S_4") (pintype "passive"))
    )
    (net (code "75") (name "Net-(X101C-KL)") (class "Default")
      (node (ref "C101") (pin "+") (pinfunction "+_+") (pintype "passive"))
      (node (ref "C102") (pin "+") (pinfunction "+_+") (pintype "passive"))
      (node (ref "C103") (pin "+") (pinfunction "+_+") (pintype "passive"))
      (node (ref "C104") (pin "+") (pinfunction "+_+") (pintype "passive"))
      (node (ref "C105") (pin "+") (pinfunction "+_+") (pintype "passive"))
      (node (ref "C18") (pin "1") (pinfunction "1_1") (pintype "passive"))
      (node (ref "D2") (pin "A") (pinfunction "A_A") (pintype "passive"))
      (node (ref "SK1A") (pin "8") (pinfunction "8_8") (pintype "passive"))
      (node (ref "SK2A") (pin "8") (pinfunction "8_8") (pintype "passive"))
      (node (ref "SK3A") (pin "8") (pinfunction "8_8") (pintype "passive"))
      (node (ref "SK4A") (pin "8") (pinfunction "8_8") (pintype "passive"))
      (node (ref "SK5A") (pin "8") (pinfunction "8_8") (pintype "passive"))
      (node (ref "X1") (pin "2") (pinfunction "S_2") (pintype "passive"))
      (node (ref "X101") (pin "2") (pinfunction "KL_2") (pintype "passive"))
      (node (ref "X101") (pin "7") (pinfunction "KL_7") (pintype "passive"))
      (node (ref "X101") (pin "9") (pinfunction "KL_9") (pintype "passive"))
    )
    (net (code "76") (name "Net-(X101E-KL)") (class "Default")
      (node (ref "C17") (pin "1") (pinfunction "1_1") (pintype "passive"))
      (node (ref "X101") (pin "4") (pinfunction "KL_4") (pintype "passive"))
      (node (ref "X101") (pin "5") (pinfunction "KL_5") (pintype "passive"))
    )
    (net (code "77") (name "unconnected-(SK1B-Pad4)") (class "Default")
      (node (ref "SK1B") (pin "4") (pinfunction "4_4") (pintype "passive"))
    )
    (net (code "78") (name "unconnected-(SK1B-Pad5)") (class "Default")
      (node (ref "SK1B") (pin "5") (pinfunction "5_5") (pintype "passive"))
    )
    (net (code "79") (name "unconnected-(SK2B-Pad4)") (class "Default")
      (node (ref "SK2B") (pin "4") (pinfunction "4_4") (pintype "passive"))
    )
    (net (code "80") (name "unconnected-(SK2B-Pad5)") (class "Default")
      (node (ref "SK2B") (pin "5") (pinfunction "5_5") (pintype "passive"))
    )
    (net (code "81") (name "unconnected-(SK3B-Pad4)") (class "Default")
      (node (ref "SK3B") (pin "4") (pinfunction "4_4") (pintype "passive"))
    )
    (net (code "82") (name "unconnected-(SK3B-Pad5)") (class "Default")
      (node (ref "SK3B") (pin "5") (pinfunction "5_5") (pintype "passive"))
    )
    (net (code "83") (name "unconnected-(SK4B-Pad4)") (class "Default")
      (node (ref "SK4B") (pin "4") (pinfunction "4_4") (pintype "passive"))
    )
    (net (code "84") (name "unconnected-(SK4B-Pad5)") (class "Default")
      (node (ref "SK4B") (pin "5") (pinfunction "5_5") (pintype "passive"))
    )
    (net (code "85") (name "unconnected-(SK5B-Pad4)") (class "Default")
      (node (ref "SK5B") (pin "4") (pinfunction "4_4") (pintype "passive"))
    )
    (net (code "86") (name "unconnected-(SK5B-Pad5)") (class "Default")
      (node (ref "SK5B") (pin "5") (pinfunction "5_5") (pintype "passive"))
    )
    (net (code "87") (name "unconnected-(U1-JTAGSEL-Pad50)") (class "Default")
      (node (ref "U1") (pin "50") (pinfunction "JTAGSEL_50") (pintype "input"))
    )
    (net (code "88") (name "unconnected-(U1-PA0{slash}PGMEN0-Pad48)") (class "Default")
      (node (ref "U1") (pin "48") (pinfunction "PA0/PGMEN0_48") (pintype "bidirectional"))
    )
    (net (code "89") (name "unconnected-(U1-PA2{slash}PGMEN2-Pad44)") (class "Default")
      (node (ref "U1") (pin "44") (pinfunction "PA2/PGMEN2_44") (pintype "bidirectional"))
    )
    (net (code "90") (name "unconnected-(U1-PA3-Pad43)") (class "Default")
      (node (ref "U1") (pin "43") (pinfunction "PA3_43") (pintype "bidirectional"))
    )
    (net (code "91") (name "unconnected-(U1-PA4{slash}PGMNCMD-Pad36)") (class "Default")
      (node (ref "U1") (pin "36") (pinfunction "PA4/PGMNCMD_36") (pintype "bidirectional"))
    )
    (net (code "92") (name "unconnected-(U1-PA5{slash}PGMRDY-Pad35)") (class "Default")
      (node (ref "U1") (pin "35") (pinfunction "PA5/PGMRDY_35") (pintype "bidirectional"))
    )
    (net (code "93") (name "unconnected-(U1-PA6{slash}PGMNOE-Pad34)") (class "Default")
      (node (ref "U1") (pin "34") (pinfunction "PA6/PGMNOE_34") (pintype "bidirectional"))
    )
    (net (code "94") (name "unconnected-(U1-PA9{slash}PGMM1-Pad30)") (class "Default")
      (node (ref "U1") (pin "30") (pinfunction "PA9/PGMM1_30") (pintype "bidirectional"))
    )
    (net (code "95") (name "unconnected-(U1-PA10{slash}PGMM2-Pad29)") (class "Default")
      (node (ref "U1") (pin "29") (pinfunction "PA10/PGMM2_29") (pintype "bidirectional"))
    )
    (net (code "96") (name "unconnected-(U1-PA11{slash}PGMM3-Pad28)") (class "Default")
      (node (ref "U1") (pin "28") (pinfunction "PA11/PGMM3_28") (pintype "bidirectional"))
    )
    (net (code "97") (name "unconnected-(U1-PA12{slash}PGMD0-Pad27)") (class "Default")
      (node (ref "U1") (pin "27") (pinfunction "PA12/PGMD0_27") (pintype "bidirectional"))
    )
    (net (code "98") (name "unconnected-(U1-PA13{slash}PGMD1-Pad22)") (class "Default")
      (node (ref "U1") (pin "22") (pinfunction "PA13/PGMD1_22") (pintype "bidirectional"))
    )
    (net (code "99") (name "unconnected-(U1-PA14{slash}PGMD2-Pad21)") (class "Default")
      (node (ref "U1") (pin "21") (pinfunction "PA14/PGMD2_21") (pintype "bidirectional"))
    )
    (net (code "100") (name "unconnected-(U1-PA15{slash}PGMD3-Pad20)") (class "Default")
      (node (ref "U1") (pin "20") (pinfunction "PA15/PGMD3_20") (pintype "bidirectional"))
    )
    (net (code "101") (name "unconnected-(U1-PA21{slash}PGMD9{slash}AD8-Pad11)") (class "Default")
      (node (ref "U1") (pin "11") (pinfunction "PA21/PGMD9/AD8_11") (pintype "bidirectional"))
    )
    (net (code "102") (name "unconnected-(U1-PA22{slash}PGMD10{slash}AD9-Pad14)") (class "Default")
      (node (ref "U1") (pin "14") (pinfunction "PA22/PGMD10/AD9_14") (pintype "bidirectional"))
    )
    (net (code "103") (name "unconnected-(U1-PA26{slash}PGMD14-Pad26)") (class "Default")
      (node (ref "U1") (pin "26") (pinfunction "PA26/PGMD14_26") (pintype "bidirectional"))
    )
    (net (code "104") (name "unconnected-(U1-PA27{slash}PGMD15-Pad37)") (class "Default")
      (node (ref "U1") (pin "37") (pinfunction "PA27/PGMD15_37") (pintype "bidirectional"))
    )
    (net (code "105") (name "unconnected-(U1-PA28-Pad38)") (class "Default")
      (node (ref "U1") (pin "38") (pinfunction "PA28_38") (pintype "bidirectional"))
    )
    (net (code "106") (name "unconnected-(U1-PA29-Pad41)") (class "Default")
      (node (ref "U1") (pin "41") (pinfunction "PA29_41") (pintype "bidirectional"))
    )
    (net (code "107") (name "unconnected-(U1-PA30-Pad42)") (class "Default")
      (node (ref "U1") (pin "42") (pinfunction "PA30_42") (pintype "bidirectional"))
    )
    (net (code "108") (name "unconnected-(U1-PA31-Pad52)") (class "Default")
      (node (ref "U1") (pin "52") (pinfunction "PA31_52") (pintype "bidirectional"))
    )
    (net (code "109") (name "unconnected-(U1-TST-Pad40)") (class "Default")
      (node (ref "U1") (pin "40") (pinfunction "TST_40") (pintype "input"))
    )
    (net (code "110") (name "unconnected-(U2D-I-Pad9)") (class "Default")
      (node (ref "U2") (pin "9") (pinfunction "I_9") (pintype "input"))
    )
    (net (code "111") (name "unconnected-(U2D-O-Pad8)") (class "Default")
      (node (ref "U2") (pin "8") (pinfunction "O_8") (pintype "output"))
    )
    (net (code "112") (name "unconnected-(U2E-I-Pad11)") (class "Default")
      (node (ref "U2") (pin "11") (pinfunction "I_11") (pintype "input"))
    )
    (net (code "113") (name "unconnected-(U2E-O-Pad10)") (class "Default")
      (node (ref "U2") (pin "10") (pinfunction "O_10") (pintype "output"))
    )
    (net (code "114") (name "unconnected-(X11-Pad1)") (class "Default")
      (node (ref "X11") (pin "1") (pinfunction "1_1") (pintype "passive"))
    )
    (net (code "115") (name "unconnected-(X11-Pad2)") (class "Default")
      (node (ref "X11") (pin "2") (pinfunction "2_2") (pintype "passive"))
    )
    (net (code "116") (name "unconnected-(X11-Pad3)") (class "Default")
      (node (ref "X11") (pin "3") (pinfunction "3_3") (pintype "passive"))
    )
    (net (code "117") (name "unconnected-(X11-Pad4)") (class "Default")
      (node (ref "X11") (pin "4") (pinfunction "4_4") (pintype "passive"))
    )
    (net (code "118") (name "unconnected-(X11-Pad5)") (class "Default")
      (node (ref "X11") (pin "5") (pinfunction "5_5") (pintype "passive"))
    )
    (net (code "119") (name "unconnected-(X11-Pad6)") (class "Default")
      (node (ref "X11") (pin "6") (pinfunction "6_6") (pintype "passive"))
    )
    (net (code "120") (name "unconnected-(X11-Pad7)") (class "Default")
      (node (ref "X11") (pin "7") (pinfunction "7_7") (pintype "passive"))
    )
    (net (code "121") (name "unconnected-(X11-Pad8)") (class "Default")
      (node (ref "X11") (pin "8") (pinfunction "8_8") (pintype "passive"))
    )
    (net (code "122") (name "unconnected-(X11-Pad9)") (class "Default")
      (node (ref "X11") (pin "9") (pinfunction "9_9") (pintype "passive"))
    )
    (net (code "123") (name "unconnected-(X11-Pad10)") (class "Default")
      (node (ref "X11") (pin "10") (pinfunction "10_10") (pintype "passive"))
    )
    (net (code "124") (name "unconnected-(X11-Pad11)") (class "Default")
      (node (ref "X11") (pin "11") (pinfunction "11_11") (pintype "passive"))
    )
    (net (code "125") (name "unconnected-(X11-Pad12)") (class "Default")
      (node (ref "X11") (pin "12") (pinfunction "12_12") (pintype "passive"))
    )
    (net (code "126") (name "unconnected-(X11-Pad13)") (class "Default")
      (node (ref "X11") (pin "13") (pinfunction "13_13") (pintype "passive"))
    )
    (net (code "127") (name "unconnected-(X11-Pad14)") (class "Default")
      (node (ref "X11") (pin "14") (pinfunction "14_14") (pintype "passive"))
    )
    (net (code "128") (name "unconnected-(X11-Pad15)") (class "Default")
      (node (ref "X11") (pin "15") (pinfunction "15_15") (pintype "passive"))
    )
    (net (code "129") (name "unconnected-(X11-Pad16)") (class "Default")
      (node (ref "X11") (pin "16") (pinfunction "16_16") (pintype "passive"))
    )
    (net (code "130") (name "unconnected-(X12-Pad1)") (class "Default")
      (node (ref "X12") (pin "1") (pinfunction "1_1") (pintype "passive"))
    )
    (net (code "131") (name "unconnected-(X12-Pad2)") (class "Default")
      (node (ref "X12") (pin "2") (pinfunction "2_2") (pintype "passive"))
    )
    (net (code "132") (name "unconnected-(X12-Pad3)") (class "Default")
      (node (ref "X12") (pin "3") (pinfunction "3_3") (pintype "passive"))
    )
    (net (code "133") (name "unconnected-(X12-Pad4)") (class "Default")
      (node (ref "X12") (pin "4") (pinfunction "4_4") (pintype "passive"))
    )
    (net (code "134") (name "unconnected-(X12-Pad5)") (class "Default")
      (node (ref "X12") (pin "5") (pinfunction "5_5") (pintype "passive"))
    )
    (net (code "135") (name "unconnected-(X12-Pad6)") (class "Default")
      (node (ref "X12") (pin "6") (pinfunction "6_6") (pintype "passive"))
    )
    (net (code "136") (name "unconnected-(X12-Pad7)") (class "Default")
      (node (ref "X12") (pin "7") (pinfunction "7_7") (pintype "passive"))
    )
    (net (code "137") (name "unconnected-(X12-Pad8)") (class "Default")
      (node (ref "X12") (pin "8") (pinfunction "8_8") (pintype "passive"))
    )
    (net (code "138") (name "unconnected-(X13-Pad1)") (class "Default")
      (node (ref "X13") (pin "1") (pinfunction "1_1") (pintype "passive"))
    )
    (net (code "139") (name "unconnected-(X13-Pad2)") (class "Default")
      (node (ref "X13") (pin "2") (pinfunction "2_2") (pintype "passive"))
    )
    (net (code "140") (name "unconnected-(X13-Pad3)") (class "Default")
      (node (ref "X13") (pin "3") (pinfunction "3_3") (pintype "passive"))
    )
    (net (code "141") (name "unconnected-(X13-Pad4)") (class "Default")
      (node (ref "X13") (pin "4") (pinfunction "4_4") (pintype "passive"))
    )
    (net (code "142") (name "unconnected-(X100-Pad4)") (class "Default")
      (node (ref "X100") (pin "4") (pinfunction "4_4") (pintype "input"))
    )
  )
)
